# solarWorldClock.net
KiCad netlist of a schematic drawn in EAGLE
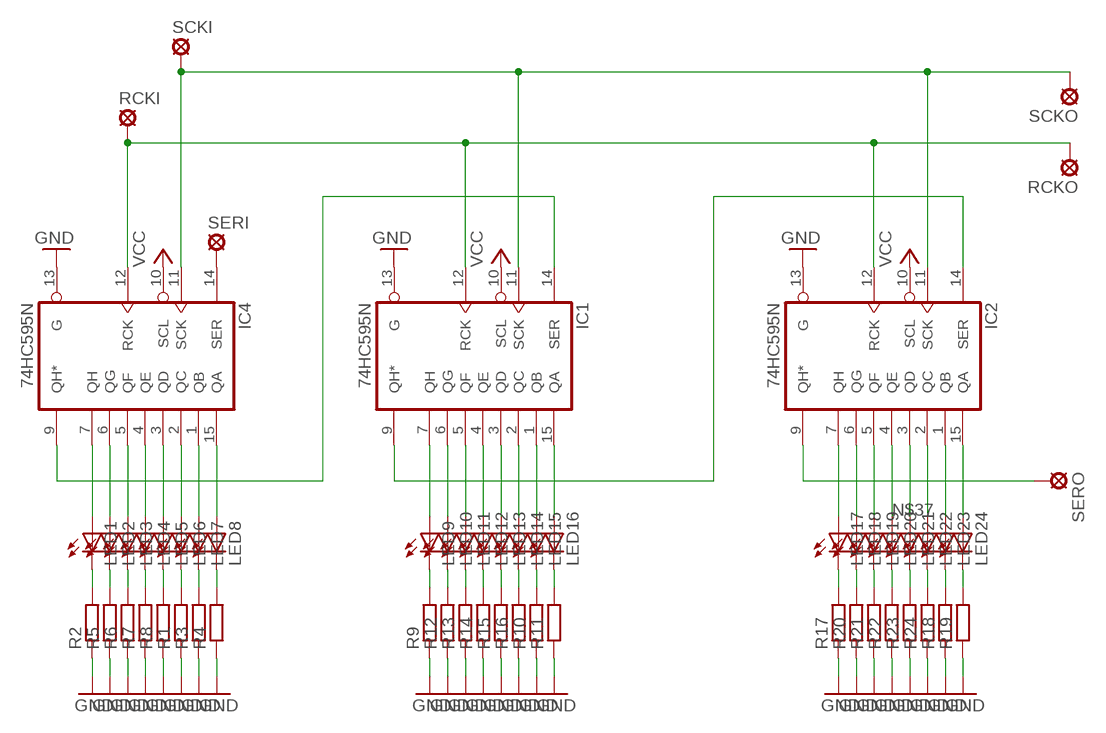
[diagram p0: schematic, sheet 1]

(export (version "E")
  (design (tool "Eeschema 10.0.6"))
  (components
    (comp (ref "IC1")
      (value "74HC595N")
      (footprint "eagle-import:DIL16")
      (libsource (lib "eagle-import") (part "74595NHC"))
    )
    (comp (ref "IC2")
      (value "74HC595N")
      (footprint "eagle-import:DIL16")
      (libsource (lib "eagle-import") (part "74595NHC"))
    )
    (comp (ref "IC4")
      (value "74HC595N")
      (footprint "eagle-import:DIL16")
      (libsource (lib "eagle-import") (part "74595NHC"))
    )
    (comp (ref "LED1")
      (value "LEDLZR181")
      (footprint "eagle-import:LZR181")
      (libsource (lib "eagle-import") (part "LEDLZR181"))
    )
    (comp (ref "LED2")
      (value "LEDLZR181")
      (footprint "eagle-import:LZR181")
      (libsource (lib "eagle-import") (part "LEDLZR181"))
    )
    (comp (ref "LED3")
      (value "LEDLZR181")
      (footprint "eagle-import:LZR181")
      (libsource (lib "eagle-import") (part "LEDLZR181"))
    )
    (comp (ref "LED4")
      (value "LEDLZR181")
      (footprint "eagle-import:LZR181")
      (libsource (lib "eagle-import") (part "LEDLZR181"))
    )
    (comp (ref "LED5")
      (value "LEDLZR181")
      (footprint "eagle-import:LZR181")
      (libsource (lib "eagle-import") (part "LEDLZR181"))
    )
    (comp (ref "LED6")
      (value "LEDLZR181")
      (footprint "eagle-import:LZR181")
      (libsource (lib "eagle-import") (part "LEDLZR181"))
    )
    (comp (ref "LED7")
      (value "LEDLZR181")
      (footprint "eagle-import:LZR181")
      (libsource (lib "eagle-import") (part "LEDLZR181"))
    )
    (comp (ref "LED8")
      (value "LEDLZR181")
      (footprint "eagle-import:LZR181")
      (libsource (lib "eagle-import") (part "LEDLZR181"))
    )
    (comp (ref "LED9")
      (value "LEDLZR181")
      (footprint "eagle-import:LZR181")
      (libsource (lib "eagle-import") (part "LEDLZR181"))
    )
    (comp (ref "LED10")
      (value "LEDLZR181")
      (footprint "eagle-import:LZR181")
      (libsource (lib "eagle-import") (part "LEDLZR181"))
    )
    (comp (ref "LED11")
      (value "LEDLZR181")
      (footprint "eagle-import:LZR181")
      (libsource (lib "eagle-import") (part "LEDLZR181"))
    )
    (comp (ref "LED12")
      (value "LEDLZR181")
      (footprint "eagle-import:LZR181")
      (libsource (lib "eagle-import") (part "LEDLZR181"))
    )
    (comp (ref "LED13")
      (value "LEDLZR181")
      (footprint "eagle-import:LZR181")
      (libsource (lib "eagle-import") (part "LEDLZR181"))
    )
    (comp (ref "LED14")
      (value "LEDLZR181")
      (footprint "eagle-import:LZR181")
      (libsource (lib "eagle-import") (part "LEDLZR181"))
    )
    (comp (ref "LED15")
      (value "LEDLZR181")
      (footprint "eagle-import:LZR181")
      (libsource (lib "eagle-import") (part "LEDLZR181"))
    )
    (comp (ref "LED16")
      (value "LEDLZR181")
      (footprint "eagle-import:LZR181")
      (libsource (lib "eagle-import") (part "LEDLZR181"))
    )
    (comp (ref "LED17")
      (value "LEDLZR181")
      (footprint "eagle-import:LZR181")
      (libsource (lib "eagle-import") (part "LEDLZR181"))
    )
    (comp (ref "LED18")
      (value "LEDLZR181")
      (footprint "eagle-import:LZR181")
      (libsource (lib "eagle-import") (part "LEDLZR181"))
    )
    (comp (ref "LED19")
      (value "LEDLZR181")
      (footprint "eagle-import:LZR181")
      (libsource (lib "eagle-import") (part "LEDLZR181"))
    )
    (comp (ref "LED20")
      (value "LEDLZR181")
      (footprint "eagle-import:LZR181")
      (libsource (lib "eagle-import") (part "LEDLZR181"))
    )
    (comp (ref "LED21")
      (value "LEDLZR181")
      (footprint "eagle-import:LZR181")
      (libsource (lib "eagle-import") (part "LEDLZR181"))
    )
    (comp (ref "LED22")
      (value "LEDLZR181")
      (footprint "eagle-import:LZR181")
      (libsource (lib "eagle-import") (part "LEDLZR181"))
    )
    (comp (ref "LED23")
      (value "LEDLZR181")
      (footprint "eagle-import:LZR181")
      (libsource (lib "eagle-import") (part "LEDLZR181"))
    )
    (comp (ref "LED24")
      (value "LEDLZR181")
      (footprint "eagle-import:LZR181")
      (libsource (lib "eagle-import") (part "LEDLZR181"))
    )
    (comp (ref "R1")
      (value "R-EU_0207/7")
      (footprint "eagle-import:0207_7")
      (libsource (lib "eagle-import") (part "R-EU_0207/7"))
    )
    (comp (ref "R2")
      (value "R-EU_0207/7")
      (footprint "eagle-import:0207_7")
      (libsource (lib "eagle-import") (part "R-EU_0207/7"))
    )
    (comp (ref "R3")
      (value "R-EU_0207/7")
      (footprint "eagle-import:0207_7")
      (libsource (lib "eagle-import") (part "R-EU_0207/7"))
    )
    (comp (ref "R4")
      (value "R-EU_0207/7")
      (footprint "eagle-import:0207_7")
      (libsource (lib "eagle-import") (part "R-EU_0207/7"))
    )
    (comp (ref "R5")
      (value "R-EU_0207/7")
      (footprint "eagle-import:0207_7")
      (libsource (lib "eagle-import") (part "R-EU_0207/7"))
    )
    (comp (ref "R6")
      (value "R-EU_0207/7")
      (footprint "eagle-import:0207_7")
      (libsource (lib "eagle-import") (part "R-EU_0207/7"))
    )
    (comp (ref "R7")
      (value "R-EU_0207/7")
      (footprint "eagle-import:0207_7")
      (libsource (lib "eagle-import") (part "R-EU_0207/7"))
    )
    (comp (ref "R8")
      (value "R-EU_0207/7")
      (footprint "eagle-import:0207_7")
      (libsource (lib "eagle-import") (part "R-EU_0207/7"))
    )
    (comp (ref "R9")
      (value "R-EU_0207/7")
      (footprint "eagle-import:0207_7")
      (libsource (lib "eagle-import") (part "R-EU_0207/7"))
    )
    (comp (ref "R10")
      (value "R-EU_0207/7")
      (footprint "eagle-import:0207_7")
      (libsource (lib "eagle-import") (part "R-EU_0207/7"))
    )
    (comp (ref "R11")
      (value "R-EU_0207/7")
      (footprint "eagle-import:0207_7")
      (libsource (lib "eagle-import") (part "R-EU_0207/7"))
    )
    (comp (ref "R12")
      (value "R-EU_0207/7")
      (footprint "eagle-import:0207_7")
      (libsource (lib "eagle-import") (part "R-EU_0207/7"))
    )
    (comp (ref "R13")
      (value "R-EU_0207/7")
      (footprint "eagle-import:0207_7")
      (libsource (lib "eagle-import") (part "R-EU_0207/7"))
    )
    (comp (ref "R14")
      (value "R-EU_0207/7")
      (footprint "eagle-import:0207_7")
      (libsource (lib "eagle-import") (part "R-EU_0207/7"))
    )
    (comp (ref "R15")
      (value "R-EU_0207/7")
      (footprint "eagle-import:0207_7")
      (libsource (lib "eagle-import") (part "R-EU_0207/7"))
    )
    (comp (ref "R16")
      (value "R-EU_0207/7")
      (footprint "eagle-import:0207_7")
      (libsource (lib "eagle-import") (part "R-EU_0207/7"))
    )
    (comp (ref "R17")
      (value "R-EU_0207/7")
      (footprint "eagle-import:0207_7")
      (libsource (lib "eagle-import") (part "R-EU_0207/7"))
    )
    (comp (ref "R18")
      (value "R-EU_0207/7")
      (footprint "eagle-import:0207_7")
      (libsource (lib "eagle-import") (part "R-EU_0207/7"))
    )
    (comp (ref "R19")
      (value "R-EU_0207/7")
      (footprint "eagle-import:0207_7")
      (libsource (lib "eagle-import") (part "R-EU_0207/7"))
    )
    (comp (ref "R20")
      (value "R-EU_0207/7")
      (footprint "eagle-import:0207_7")
      (libsource (lib "eagle-import") (part "R-EU_0207/7"))
    )
    (comp (ref "R21")
      (value "R-EU_0207/7")
      (footprint "eagle-import:0207_7")
      (libsource (lib "eagle-import") (part "R-EU_0207/7"))
    )
    (comp (ref "R22")
      (value "R-EU_0207/7")
      (footprint "eagle-import:0207_7")
      (libsource (lib "eagle-import") (part "R-EU_0207/7"))
    )
    (comp (ref "R23")
      (value "R-EU_0207/7")
      (footprint "eagle-import:0207_7")
      (libsource (lib "eagle-import") (part "R-EU_0207/7"))
    )
    (comp (ref "R24")
      (value "R-EU_0207/7")
      (footprint "eagle-import:0207_7")
      (libsource (lib "eagle-import") (part "R-EU_0207/7"))
    )
    (comp (ref "RCKI")
      (value "LSP10")
      (footprint "eagle-import:LSP10")
      (libsource (lib "eagle-import") (part "LSP10"))
    )
    (comp (ref "RCKO")
      (value "LSP10")
      (footprint "eagle-import:LSP10")
      (libsource (lib "eagle-import") (part "LSP10"))
    )
    (comp (ref "SCKI")
      (value "LSP10")
      (footprint "eagle-import:LSP10")
      (libsource (lib "eagle-import") (part "LSP10"))
    )
    (comp (ref "SCKO")
      (value "LSP10")
      (footprint "eagle-import:LSP10")
      (libsource (lib "eagle-import") (part "LSP10"))
    )
    (comp (ref "SERI")
      (value "LSP10")
      (footprint "eagle-import:LSP10")
      (libsource (lib "eagle-import") (part "LSP10"))
    )
    (comp (ref "SERO")
      (value "LSP10")
      (footprint "eagle-import:LSP10")
      (libsource (lib "eagle-import") (part "LSP10"))
    )
  )
  (nets
    (net (code "1") (name "/N$37") (class "Default")
      (node (ref "IC2") (pin "5") (pinfunction "QF_5") (pintype "tri_state"))
      (node (ref "LED19") (pin "A") (pinfunction "A_A") (pintype "passive"))
    )
    (net (code "2") (name "GND") (class "Default")
      (node (ref "IC1") (pin "13") (pinfunction "G_13") (pintype "input"))
      (node (ref "IC2") (pin "13") (pinfunction "G_13") (pintype "input"))
      (node (ref "IC4") (pin "13") (pinfunction "G_13") (pintype "input"))
      (node (ref "R1") (pin "1") (pinfunction "1_1") (pintype "passive"))
      (node (ref "R10") (pin "1") (pinfunction "1_1") (pintype "passive"))
      (node (ref "R11") (pin "1") (pinfunction "1_1") (pintype "passive"))
      (node (ref "R12") (pin "1") (pinfunction "1_1") (pintype "passive"))
      (node (ref "R13") (pin "1") (pinfunction "1_1") (pintype "passive"))
      (node (ref "R14") (pin "1") (pinfunction "1_1") (pintype "passive"))
      (node (ref "R15") (pin "1") (pinfunction "1_1") (pintype "passive"))
      (node (ref "R16") (pin "1") (pinfunction "1_1") (pintype "passive"))
      (node (ref "R17") (pin "1") (pinfunction "1_1") (pintype "passive"))
      (node (ref "R18") (pin "1") (pinfunction "1_1") (pintype "passive"))
      (node (ref "R19") (pin "1") (pinfunction "1_1") (pintype "passive"))
      (node (ref "R2") (pin "1") (pinfunction "1_1") (pintype "passive"))
      (node (ref "R20") (pin "1") (pinfunction "1_1") (pintype "passive"))
      (node (ref "R21") (pin "1") (pinfunction "1_1") (pintype "passive"))
      (node (ref "R22") (pin "1") (pinfunction "1_1") (pintype "passive"))
      (node (ref "R23") (pin "1") (pinfunction "1_1") (pintype "passive"))
      (node (ref "R24") (pin "1") (pinfunction "1_1") (pintype "passive"))
      (node (ref "R3") (pin "1") (pinfunction "1_1") (pintype "passive"))
      (node (ref "R4") (pin "1") (pinfunction "1_1") (pintype "passive"))
      (node (ref "R5") (pin "1") (pinfunction "1_1") (pintype "passive"))
      (node (ref "R6") (pin "1") (pinfunction "1_1") (pintype "passive"))
      (node (ref "R7") (pin "1") (pinfunction "1_1") (pintype "passive"))
      (node (ref "R8") (pin "1") (pinfunction "1_1") (pintype "passive"))
      (node (ref "R9") (pin "1") (pinfunction "1_1") (pintype "passive"))
    )
    (net (code "3") (name "Net-(IC1A-QA)") (class "Default")
      (node (ref "IC1") (pin "15") (pinfunction "QA_15") (pintype "tri_state"))
      (node (ref "LED16") (pin "A") (pinfunction "A_A") (pintype "passive"))
    )
    (net (code "4") (name "Net-(IC1A-QB)") (class "Default")
      (node (ref "IC1") (pin "1") (pinfunction "QB_1") (pintype "tri_state"))
      (node (ref "LED15") (pin "A") (pinfunction "A_A") (pintype "passive"))
    )
    (net (code "5") (name "Net-(IC1A-QC)") (class "Default")
      (node (ref "IC1") (pin "2") (pinfunction "QC_2") (pintype "tri_state"))
      (node (ref "LED14") (pin "A") (pinfunction "A_A") (pintype "passive"))
    )
    (net (code "6") (name "Net-(IC1A-QD)") (class "Default")
      (node (ref "IC1") (pin "3") (pinfunction "QD_3") (pintype "tri_state"))
      (node (ref "LED13") (pin "A") (pinfunction "A_A") (pintype "passive"))
    )
    (net (code "7") (name "Net-(IC1A-QE)") (class "Default")
      (node (ref "IC1") (pin "4") (pinfunction "QE_4") (pintype "tri_state"))
      (node (ref "LED12") (pin "A") (pinfunction "A_A") (pintype "passive"))
    )
    (net (code "8") (name "Net-(IC1A-QF)") (class "Default")
      (node (ref "IC1") (pin "5") (pinfunction "QF_5") (pintype "tri_state"))
      (node (ref "LED11") (pin "A") (pinfunction "A_A") (pintype "passive"))
    )
    (net (code "9") (name "Net-(IC1A-QG)") (class "Default")
      (node (ref "IC1") (pin "6") (pinfunction "QG_6") (pintype "tri_state"))
      (node (ref "LED10") (pin "A") (pinfunction "A_A") (pintype "passive"))
    )
    (net (code "10") (name "Net-(IC1A-QH)") (class "Default")
      (node (ref "IC1") (pin "7") (pinfunction "QH_7") (pintype "tri_state"))
      (node (ref "LED9") (pin "A") (pinfunction "A_A") (pintype "passive"))
    )
    (net (code "11") (name "Net-(IC1A-QH*)") (class "Default")
      (node (ref "IC1") (pin "9") (pinfunction "QH*_9") (pintype "tri_state"))
      (node (ref "IC2") (pin "14") (pinfunction "SER_14") (pintype "input"))
    )
    (net (code "12") (name "Net-(IC1A-RCK)") (class "Default")
      (node (ref "IC1") (pin "12") (pinfunction "RCK_12") (pintype "input"))
      (node (ref "IC2") (pin "12") (pinfunction "RCK_12") (pintype "input"))
      (node (ref "IC4") (pin "12") (pinfunction "RCK_12") (pintype "input"))
      (node (ref "RCKI") (pin "MP") (pinfunction "MP_MP") (pintype "passive"))
      (node (ref "RCKO") (pin "MP") (pinfunction "MP_MP") (pintype "passive"))
    )
    (net (code "13") (name "Net-(IC1A-SCK)") (class "Default")
      (node (ref "IC1") (pin "11") (pinfunction "SCK_11") (pintype "input"))
      (node (ref "IC2") (pin "11") (pinfunction "SCK_11") (pintype "input"))
      (node (ref "IC4") (pin "11") (pinfunction "SCK_11") (pintype "input"))
      (node (ref "SCKI") (pin "MP") (pinfunction "MP_MP") (pintype "passive"))
      (node (ref "SCKO") (pin "MP") (pinfunction "MP_MP") (pintype "passive"))
    )
    (net (code "14") (name "Net-(IC1A-SER)") (class "Default")
      (node (ref "IC1") (pin "14") (pinfunction "SER_14") (pintype "input"))
      (node (ref "IC4") (pin "9") (pinfunction "QH*_9") (pintype "tri_state"))
    )
    (net (code "15") (name "Net-(IC2A-QA)") (class "Default")
      (node (ref "IC2") (pin "15") (pinfunction "QA_15") (pintype "tri_state"))
      (node (ref "LED24") (pin "A") (pinfunction "A_A") (pintype "passive"))
    )
    (net (code "16") (name "Net-(IC2A-QB)") (class "Default")
      (node (ref "IC2") (pin "1") (pinfunction "QB_1") (pintype "tri_state"))
      (node (ref "LED23") (pin "A") (pinfunction "A_A") (pintype "passive"))
    )
    (net (code "17") (name "Net-(IC2A-QC)") (class "Default")
      (node (ref "IC2") (pin "2") (pinfunction "QC_2") (pintype "tri_state"))
      (node (ref "LED22") (pin "A") (pinfunction "A_A") (pintype "passive"))
    )
    (net (code "18") (name "Net-(IC2A-QD)") (class "Default")
      (node (ref "IC2") (pin "3") (pinfunction "QD_3") (pintype "tri_state"))
      (node (ref "LED21") (pin "A") (pinfunction "A_A") (pintype "passive"))
    )
    (net (code "19") (name "Net-(IC2A-QE)") (class "Default")
      (node (ref "IC2") (pin "4") (pinfunction "QE_4") (pintype "tri_state"))
      (node (ref "LED20") (pin "A") (pinfunction "A_A") (pintype "passive"))
    )
    (net (code "20") (name "Net-(IC2A-QG)") (class "Default")
      (node (ref "IC2") (pin "6") (pinfunction "QG_6") (pintype "tri_state"))
      (node (ref "LED18") (pin "A") (pinfunction "A_A") (pintype "passive"))
    )
    (net (code "21") (name "Net-(IC2A-QH)") (class "Default")
      (node (ref "IC2") (pin "7") (pinfunction "QH_7") (pintype "tri_state"))
      (node (ref "LED17") (pin "A") (pinfunction "A_A") (pintype "passive"))
    )
    (net (code "22") (name "Net-(IC2A-QH*)") (class "Default")
      (node (ref "IC2") (pin "9") (pinfunction "QH*_9") (pintype "tri_state"))
      (node (ref "SERO") (pin "MP") (pinfunction "MP_MP") (pintype "passive"))
    )
    (net (code "23") (name "Net-(IC4A-QA)") (class "Default")
      (node (ref "IC4") (pin "15") (pinfunction "QA_15") (pintype "tri_state"))
      (node (ref "LED8") (pin "A") (pinfunction "A_A") (pintype "passive"))
    )
    (net (code "24") (name "Net-(IC4A-QB)") (class "Default")
      (node (ref "IC4") (pin "1") (pinfunction "QB_1") (pintype "tri_state"))
      (node (ref "LED7") (pin "A") (pinfunction "A_A") (pintype "passive"))
    )
    (net (code "25") (name "Net-(IC4A-QC)") (class "Default")
      (node (ref "IC4") (pin "2") (pinfunction "QC_2") (pintype "tri_state"))
      (node (ref "LED6") (pin "A") (pinfunction "A_A") (pintype "passive"))
    )
    (net (code "26") (name "Net-(IC4A-QD)") (class "Default")
      (node (ref "IC4") (pin "3") (pinfunction "QD_3") (pintype "tri_state"))
      (node (ref "LED5") (pin "A") (pinfunction "A_A") (pintype "passive"))
    )
    (net (code "27") (name "Net-(IC4A-QE)") (class "Default")
      (node (ref "IC4") (pin "4") (pinfunction "QE_4") (pintype "tri_state"))
      (node (ref "LED4") (pin "A") (pinfunction "A_A") (pintype "passive"))
    )
    (net (code "28") (name "Net-(IC4A-QF)") (class "Default")
      (node (ref "IC4") (pin "5") (pinfunction "QF_5") (pintype "tri_state"))
      (node (ref "LED3") (pin "A") (pinfunction "A_A") (pintype "passive"))
    )
    (net (code "29") (name "Net-(IC4A-QG)") (class "Default")
      (node (ref "IC4") (pin "6") (pinfunction "QG_6") (pintype "tri_state"))
      (node (ref "LED2") (pin "A") (pinfunction "A_A") (pintype "passive"))
    )
    (net (code "30") (name "Net-(IC4A-QH)") (class "Default")
      (node (ref "IC4") (pin "7") (pinfunction "QH_7") (pintype "tri_state"))
      (node (ref "LED1") (pin "A") (pinfunction "A_A") (pintype "passive"))
    )
    (net (code "31") (name "Net-(IC4A-SER)") (class "Default")
      (node (ref "IC4") (pin "14") (pinfunction "SER_14") (pintype "input"))
      (node (ref "SERI") (pin "MP") (pinfunction "MP_MP") (pintype "passive"))
    )
    (net (code "32") (name "Net-(LED1-C)") (class "Default")
      (node (ref "LED1") (pin "K") (pinfunction "C_K") (pintype "passive"))
      (node (ref "R2") (pin "2") (pinfunction "2_2") (pintype "passive"))
    )
    (net (code "33") (name "Net-(LED2-C)") (class "Default")
      (node (ref "LED2") (pin "K") (pinfunction "C_K") (pintype "passive"))
      (node (ref "R5") (pin "2") (pinfunction "2_2") (pintype "passive"))
    )
    (net (code "34") (name "Net-(LED3-C)") (class "Default")
      (node (ref "LED3") (pin "K") (pinfunction "C_K") (pintype "passive"))
      (node (ref "R6") (pin "2") (pinfunction "2_2") (pintype "passive"))
    )
    (net (code "35") (name "Net-(LED4-C)") (class "Default")
      (node (ref "LED4") (pin "K") (pinfunction "C_K") (pintype "passive"))
      (node (ref "R7") (pin "2") (pinfunction "2_2") (pintype "passive"))
    )
    (net (code "36") (name "Net-(LED5-C)") (class "Default")
      (node (ref "LED5") (pin "K") (pinfunction "C_K") (pintype "passive"))
      (node (ref "R8") (pin "2") (pinfunction "2_2") (pintype "passive"))
    )
    (net (code "37") (name "Net-(LED6-C)") (class "Default")
      (node (ref "LED6") (pin "K") (pinfunction "C_K") (pintype "passive"))
      (node (ref "R1") (pin "2") (pinfunction "2_2") (pintype "passive"))
    )
    (net (code "38") (name "Net-(LED7-C)") (class "Default")
      (node (ref "LED7") (pin "K") (pinfunction "C_K") (pintype "passive"))
      (node (ref "R3") (pin "2") (pinfunction "2_2") (pintype "passive"))
    )
    (net (code "39") (name "Net-(LED8-C)") (class "Default")
      (node (ref "LED8") (pin "K") (pinfunction "C_K") (pintype "passive"))
      (node (ref "R4") (pin "2") (pinfunction "2_2") (pintype "passive"))
    )
    (net (code "40") (name "Net-(LED9-C)") (class "Default")
      (node (ref "LED9") (pin "K") (pinfunction "C_K") (pintype "passive"))
      (node (ref "R9") (pin "2") (pinfunction "2_2") (pintype "passive"))
    )
    (net (code "41") (name "Net-(LED10-C)") (class "Default")
      (node (ref "LED10") (pin "K") (pinfunction "C_K") (pintype "passive"))
      (node (ref "R12") (pin "2") (pinfunction "2_2") (pintype "passive"))
    )
    (net (code "42") (name "Net-(LED11-C)") (class "Default")
      (node (ref "LED11") (pin "K") (pinfunction "C_K") (pintype "passive"))
      (node (ref "R13") (pin "2") (pinfunction "2_2") (pintype "passive"))
    )
    (net (code "43") (name "Net-(LED12-C)") (class "Default")
      (node (ref "LED12") (pin "K") (pinfunction "C_K") (pintype "passive"))
      (node (ref "R14") (pin "2") (pinfunction "2_2") (pintype "passive"))
    )
    (net (code "44") (name "Net-(LED13-C)") (class "Default")
      (node (ref "LED13") (pin "K") (pinfunction "C_K") (pintype "passive"))
      (node (ref "R15") (pin "2") (pinfunction "2_2") (pintype "passive"))
    )
    (net (code "45") (name "Net-(LED14-C)") (class "Default")
      (node (ref "LED14") (pin "K") (pinfunction "C_K") (pintype "passive"))
      (node (ref "R16") (pin "2") (pinfunction "2_2") (pintype "passive"))
    )
    (net (code "46") (name "Net-(LED15-C)") (class "Default")
      (node (ref "LED15") (pin "K") (pinfunction "C_K") (pintype "passive"))
      (node (ref "R10") (pin "2") (pinfunction "2_2") (pintype "passive"))
    )
    (net (code "47") (name "Net-(LED16-C)") (class "Default")
      (node (ref "LED16") (pin "K") (pinfunction "C_K") (pintype "passive"))
      (node (ref "R11") (pin "2") (pinfunction "2_2") (pintype "passive"))
    )
    (net (code "48") (name "Net-(LED17-C)") (class "Default")
      (node (ref "LED17") (pin "K") (pinfunction "C_K") (pintype "passive"))
      (node (ref "R17") (pin "2") (pinfunction "2_2") (pintype "passive"))
    )
    (net (code "49") (name "Net-(LED18-C)") (class "Default")
      (node (ref "LED18") (pin "K") (pinfunction "C_K") (pintype "passive"))
      (node (ref "R20") (pin "2") (pinfunction "2_2") (pintype "passive"))
    )
    (net (code "50") (name "Net-(LED19-C)") (class "Default")
      (node (ref "LED19") (pin "K") (pinfunction "C_K") (pintype "passive"))
      (node (ref "R21") (pin "2") (pinfunction "2_2") (pintype "passive"))
    )
    (net (code "51") (name "Net-(LED20-C)") (class "Default")
      (node (ref "LED20") (pin "K") (pinfunction "C_K") (pintype "passive"))
      (node (ref "R22") (pin "2") (pinfunction "2_2") (pintype "passive"))
    )
    (net (code "52") (name "Net-(LED21-C)") (class "Default")
      (node (ref "LED21") (pin "K") (pinfunction "C_K") (pintype "passive"))
      (node (ref "R23") (pin "2") (pinfunction "2_2") (pintype "passive"))
    )
    (net (code "53") (name "Net-(LED22-C)") (class "Default")
      (node (ref "LED22") (pin "K") (pinfunction "C_K") (pintype "passive"))
      (node (ref "R24") (pin "2") (pinfunction "2_2") (pintype "passive"))
    )
    (net (code "54") (name "Net-(LED23-C)") (class "Default")
      (node (ref "LED23") (pin "K") (pinfunction "C_K") (pintype "passive"))
      (node (ref "R18") (pin "2") (pinfunction "2_2") (pintype "passive"))
    )
    (net (code "55") (name "Net-(LED24-C)") (class "Default")
      (node (ref "LED24") (pin "K") (pinfunction "C_K") (pintype "passive"))
      (node (ref "R19") (pin "2") (pinfunction "2_2") (pintype "passive"))
    )
    (net (code "56") (name "VCC") (class "Default")
      (node (ref "IC1") (pin "10") (pinfunction "SCL_10") (pintype "input"))
      (node (ref "IC2") (pin "10") (pinfunction "SCL_10") (pintype "input"))
      (node (ref "IC4") (pin "10") (pinfunction "SCL_10") (pintype "input"))
    )
  )
)
